# Top.net
KiCad netlist of a schematic drawn in Altium Designer
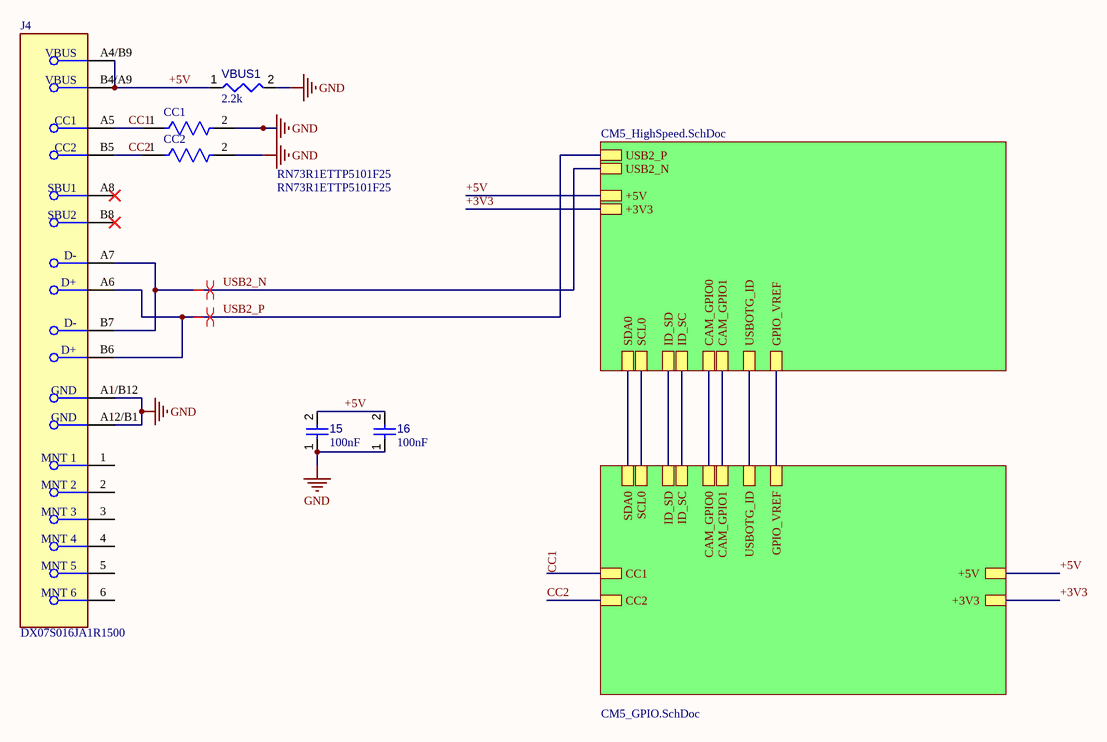
[diagram p0: Top.SchDoc]

(export (version "E")
  (design (tool "Eeschema 10.0.6"))
  (components
    (comp (ref "15")
      (value "100nF")
      (footprint "CAPC0402(1005)60_L")
      (description "Chip Capacitor, 100nF +/-20%, 50V, 0402, Thickness 0.6 mm")
      (fields (field (name "TOLERANCE") "10%") (field (name "Comment") "Capacitor 100nF +/-20% 50V 0402"))
      (libsource (lib "Rudra Navdiya") (part "CAP-NP-2"))
    )
    (comp (ref "16")
      (value "100nF")
      (footprint "CAPC0402(1005)60_L")
      (description "Chip Capacitor, 100nF +/-20%, 50V, 0402, Thickness 0.6 mm")
      (fields (field (name "TOLERANCE") "10%") (field (name "Comment") "Capacitor 100nF +/-20% 50V 0402"))
      (libsource (lib "Rudra Navdiya") (part "CAP-NP-2"))
    )
    (comp (ref "CC1")
      (value "RN73R1ETTP5101F25")
      (footprint "FP-RN73R1E-IPC_C")
      (description "5.1kΩ ±1% 0.063W, 1/16W Chip Resistor 0402 (1005 Metric) Moisture Resistant Thin Film")
      (libsource (lib "Altium Content Vault") (part "1029c3af85768c4190bb7ad29bc67b5"))
    )
    (comp (ref "CC2")
      (value "RN73R1ETTP5101F25")
      (footprint "FP-RN73R1E-IPC_C")
      (description "5.1kΩ ±1% 0.063W, 1/16W Chip Resistor 0402 (1005 Metric) Moisture Resistant Thin Film")
      (libsource (lib "Altium Content Vault") (part "1029c3af85768c4190bb7ad29bc67b5"))
    )
    (comp (ref "J4")
      (value "DX07S016JA1R1500")
      (footprint "FP-DX07S016JA1R1500-MFG")
      (description "CONN RCP USB2.0 TYP C 24P SMD RA")
      (libsource (lib "Altium Content Vault") (part "7f3e9989102a0f22bff9cb010881d34"))
    )
    (comp (ref "VBUS1")
      (value "2.2k")
      (footprint "RESC0402(1005)_L")
      (description "2K2 0.063W 5% 0402 (1005 Metric)  SMD")
      (fields (field (name "TOLERANCE") "5%") (field (name "POWER") "63mW"))
      (libsource (lib "Rudra Navdiya") (part "2D2KR2J"))
    )
  )
  (nets
    (net (code "2") (name "/+5V") (class "Default")
      (node (ref "15") (pin "2") (pinfunction "2_2") (pintype "passive"))
      (node (ref "16") (pin "2") (pinfunction "2_2") (pintype "passive"))
      (node (ref "J4") (pin "A4/B9") (pinfunction "VBUS_A4/B9") (pintype "power_in"))
      (node (ref "J4") (pin "B4/A9") (pinfunction "VBUS_B4/A9") (pintype "power_in"))
      (node (ref "VBUS1") (pin "1") (pinfunction "1_1") (pintype "passive"))
    )
    (net (code "5") (name "/CC1") (class "Default")
      (node (ref "CC1") (pin "1") (pinfunction "1_1") (pintype "passive"))
      (node (ref "J4") (pin "A5") (pinfunction "CC1_A5") (pintype "passive"))
    )
    (net (code "6") (name "/CC2") (class "Default")
      (node (ref "CC2") (pin "1") (pinfunction "1_1") (pintype "passive"))
      (node (ref "J4") (pin "B5") (pinfunction "CC2_B5") (pintype "passive"))
    )
    (net (code "12") (name "/USB2_N") (class "Default")
      (node (ref "J4") (pin "A7") (pinfunction "D-_A7") (pintype "passive"))
      (node (ref "J4") (pin "B7") (pinfunction "D-_B7") (pintype "passive"))
    )
    (net (code "13") (name "/USB2_P") (class "Default")
      (node (ref "J4") (pin "A6") (pinfunction "D+_A6") (pintype "passive"))
      (node (ref "J4") (pin "B6") (pinfunction "D+_B6") (pintype "passive"))
    )
    (net (code "15") (name "GND") (class "Default")
      (node (ref "15") (pin "1") (pinfunction "1_1") (pintype "passive"))
      (node (ref "16") (pin "1") (pinfunction "1_1") (pintype "passive"))
      (node (ref "CC1") (pin "2") (pinfunction "2_2") (pintype "passive"))
      (node (ref "CC2") (pin "2") (pinfunction "2_2") (pintype "passive"))
      (node (ref "J4") (pin "A1/B12") (pinfunction "GND_A1/B12") (pintype "power_in"))
      (node (ref "J4") (pin "A12/B1") (pinfunction "GND_A12/B1") (pintype "power_in"))
      (node (ref "VBUS1") (pin "2") (pinfunction "2_2") (pintype "passive"))
    )
    (net (code "16") (name "unconnected-(J4-MNT_1-Pad1)") (class "Default")
      (node (ref "J4") (pin "1") (pinfunction "MNT_1_1") (pintype "passive"))
    )
    (net (code "17") (name "unconnected-(J4-MNT_2-Pad2)") (class "Default")
      (node (ref "J4") (pin "2") (pinfunction "MNT_2_2") (pintype "passive"))
    )
    (net (code "18") (name "unconnected-(J4-MNT_3-Pad3)") (class "Default")
      (node (ref "J4") (pin "3") (pinfunction "MNT_3_3") (pintype "passive"))
    )
    (net (code "19") (name "unconnected-(J4-MNT_4-Pad4)") (class "Default")
      (node (ref "J4") (pin "4") (pinfunction "MNT_4_4") (pintype "passive"))
    )
    (net (code "20") (name "unconnected-(J4-MNT_5-Pad5)") (class "Default")
      (node (ref "J4") (pin "5") (pinfunction "MNT_5_5") (pintype "passive"))
    )
    (net (code "21") (name "unconnected-(J4-MNT_6-Pad6)") (class "Default")
      (node (ref "J4") (pin "6") (pinfunction "MNT_6_6") (pintype "passive"))
    )
    (net (code "22") (name "unconnected-(J4-SBU1-PadA8)") (class "Default")
      (node (ref "J4") (pin "A8") (pinfunction "SBU1_A8") (pintype "passive+no_connect"))
    )
    (net (code "23") (name "unconnected-(J4-SBU2-PadB8)") (class "Default")
      (node (ref "J4") (pin "B8") (pinfunction "SBU2_B8") (pintype "passive+no_connect"))
    )
  )
)
